# morkscam.net
KiCad netlist of a schematic drawn in EAGLE
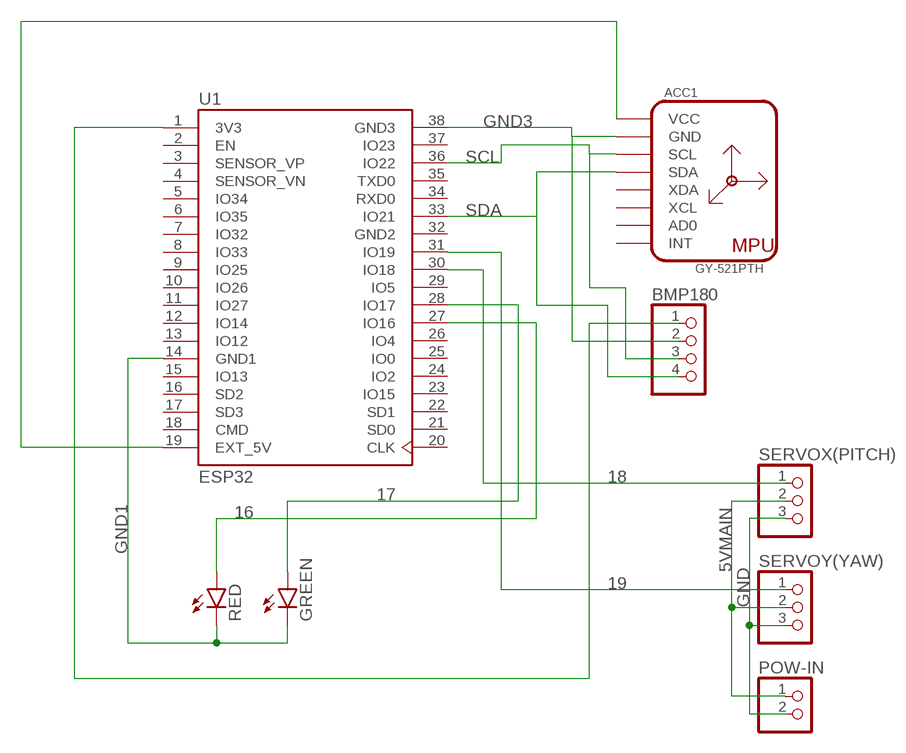
[diagram p0: schematic, sheet 1]

(export (version "E")
  (design (tool "Eeschema 10.0.6"))
  (components
    (comp (ref "ACC1")
      (value "GY-521PTH")
      (footprint "eagle-import:GY-521")
      (fields (field (name "MF") "GODREAM FORDREAM CO., LIMITED") (field (name "MP") "GY-521"))
      (libsource (lib "eagle-import") (part "GY-521PTH"))
    )
    (comp (ref "BMP180")
      (value "PINHD-1X4")
      (footprint "eagle-import:1X04")
      (libsource (lib "eagle-import") (part "PINHD-1X4"))
    )
    (comp (ref "GREEN")
      (value "LED3MM")
      (footprint "eagle-import:LED3MM")
      (libsource (lib "eagle-import") (part "LED3MM"))
    )
    (comp (ref "POW-IN")
      (value "PINHD-1X2")
      (footprint "eagle-import:1X02")
      (libsource (lib "eagle-import") (part "PINHD-1X2"))
    )
    (comp (ref "RED")
      (value "LED3MM")
      (footprint "eagle-import:LED3MM")
      (libsource (lib "eagle-import") (part "LED3MM"))
    )
    (comp (ref "SERVOX(PITCH)")
      (value "PINHD-1X3")
      (footprint "eagle-import:1X03")
      (libsource (lib "eagle-import") (part "PINHD-1X3"))
    )
    (comp (ref "SERVOY(YAW)")
      (value "PINHD-1X3")
      (footprint "eagle-import:1X03")
      (libsource (lib "eagle-import") (part "PINHD-1X3"))
    )
    (comp (ref "U1")
      (value "ESP32")
      (footprint "eagle-import:MODULE_ESP32-DEVKITC")
      (fields (field (name "MF") "Espressif Systems") (field (name "MP") "ESP32-DEVKITC"))
      (libsource (lib "eagle-import") (part "ESP32"))
    )
  )
  (nets
    (net (code "1") (name "/5VMAIN") (class "Default")
      (node (ref "POW-IN") (pin "1") (pinfunction "1_1") (pintype "passive"))
      (node (ref "SERVOX(PITCH)") (pin "2") (pinfunction "2_2") (pintype "passive"))
      (node (ref "SERVOY(YAW)") (pin "2") (pinfunction "2_2") (pintype "passive"))
    )
    (net (code "2") (name "/16") (class "Default")
      (node (ref "RED") (pin "A") (pinfunction "A_A") (pintype "passive"))
      (node (ref "U1") (pin "27") (pinfunction "IO16_27") (pintype "bidirectional"))
    )
    (net (code "3") (name "/17") (class "Default")
      (node (ref "GREEN") (pin "A") (pinfunction "A_A") (pintype "passive"))
      (node (ref "U1") (pin "28") (pinfunction "IO17_28") (pintype "bidirectional"))
    )
    (net (code "4") (name "/18") (class "Default")
      (node (ref "SERVOX(PITCH)") (pin "1") (pinfunction "1_1") (pintype "passive"))
      (node (ref "U1") (pin "30") (pinfunction "IO18_30") (pintype "bidirectional"))
    )
    (net (code "5") (name "/19") (class "Default")
      (node (ref "SERVOY(YAW)") (pin "1") (pinfunction "1_1") (pintype "passive"))
      (node (ref "U1") (pin "31") (pinfunction "IO19_31") (pintype "bidirectional"))
    )
    (net (code "6") (name "/GND") (class "Default")
      (node (ref "POW-IN") (pin "2") (pinfunction "2_2") (pintype "passive"))
      (node (ref "SERVOX(PITCH)") (pin "3") (pinfunction "3_3") (pintype "passive"))
      (node (ref "SERVOY(YAW)") (pin "3") (pinfunction "3_3") (pintype "passive"))
    )
    (net (code "7") (name "/GND1") (class "Default")
      (node (ref "GREEN") (pin "K") (pinfunction "C_K") (pintype "passive"))
      (node (ref "RED") (pin "K") (pinfunction "C_K") (pintype "passive"))
      (node (ref "U1") (pin "14") (pinfunction "GND1_14") (pintype "power_in"))
    )
    (net (code "8") (name "/GND2") (class "Default")
      (node (ref "U1") (pin "32") (pinfunction "GND2_32") (pintype "power_in"))
    )
    (net (code "9") (name "/GND3") (class "Default")
      (node (ref "ACC1") (pin "GND") (pinfunction "GND_GND") (pintype "power_in"))
      (node (ref "BMP180") (pin "2") (pinfunction "2_2") (pintype "passive"))
      (node (ref "U1") (pin "38") (pinfunction "GND3_38") (pintype "power_in"))
    )
    (net (code "10") (name "/SCL") (class "Default")
      (node (ref "ACC1") (pin "SCL") (pinfunction "SCL_SCL") (pintype "bidirectional"))
      (node (ref "BMP180") (pin "3") (pinfunction "3_3") (pintype "passive"))
      (node (ref "U1") (pin "36") (pinfunction "IO22_36") (pintype "bidirectional"))
    )
    (net (code "11") (name "/SDA") (class "Default")
      (node (ref "ACC1") (pin "SDA") (pinfunction "SDA_SDA") (pintype "bidirectional"))
      (node (ref "BMP180") (pin "4") (pinfunction "4_4") (pintype "passive"))
      (node (ref "U1") (pin "33") (pinfunction "IO21_33") (pintype "bidirectional"))
    )
    (net (code "12") (name "Net-(U1-3V3)") (class "Default")
      (node (ref "BMP180") (pin "1") (pinfunction "1_1") (pintype "passive"))
      (node (ref "U1") (pin "1") (pinfunction "3V3_1") (pintype "power_in"))
    )
    (net (code "13") (name "Net-(U1-EXT_5V)") (class "Default")
      (node (ref "ACC1") (pin "VCC") (pinfunction "VCC_VCC") (pintype "power_in"))
      (node (ref "U1") (pin "19") (pinfunction "EXT_5V_19") (pintype "power_in"))
    )
    (net (code "14") (name "unconnected-(ACC1-PadAD0)") (class "Default")
      (node (ref "ACC1") (pin "AD0") (pinfunction "AD0_AD0") (pintype "bidirectional"))
    )
    (net (code "15") (name "unconnected-(ACC1-PadINT)") (class "Default")
      (node (ref "ACC1") (pin "INT") (pinfunction "INT_INT") (pintype "bidirectional"))
    )
    (net (code "16") (name "unconnected-(ACC1-PadXCL)") (class "Default")
      (node (ref "ACC1") (pin "XCL") (pinfunction "XCL_XCL") (pintype "bidirectional"))
    )
    (net (code "17") (name "unconnected-(ACC1-PadXDA)") (class "Default")
      (node (ref "ACC1") (pin "XDA") (pinfunction "XDA_XDA") (pintype "bidirectional"))
    )
    (net (code "18") (name "unconnected-(U1-CLK-Pad20)") (class "Default")
      (node (ref "U1") (pin "20") (pinfunction "CLK_20") (pintype "input"))
    )
    (net (code "19") (name "unconnected-(U1-CMD-Pad18)") (class "Default")
      (node (ref "U1") (pin "18") (pinfunction "CMD_18") (pintype "bidirectional"))
    )
    (net (code "20") (name "unconnected-(U1-EN-Pad2)") (class "Default")
      (node (ref "U1") (pin "2") (pinfunction "EN_2") (pintype "input"))
    )
    (net (code "21") (name "unconnected-(U1-IO0-Pad25)") (class "Default")
      (node (ref "U1") (pin "25") (pinfunction "IO0_25") (pintype "bidirectional"))
    )
    (net (code "22") (name "unconnected-(U1-IO2-Pad24)") (class "Default")
      (node (ref "U1") (pin "24") (pinfunction "IO2_24") (pintype "bidirectional"))
    )
    (net (code "23") (name "unconnected-(U1-IO4-Pad26)") (class "Default")
      (node (ref "U1") (pin "26") (pinfunction "IO4_26") (pintype "bidirectional"))
    )
    (net (code "24") (name "unconnected-(U1-IO5-Pad29)") (class "Default")
      (node (ref "U1") (pin "29") (pinfunction "IO5_29") (pintype "bidirectional"))
    )
    (net (code "25") (name "unconnected-(U1-IO12-Pad13)") (class "Default")
      (node (ref "U1") (pin "13") (pinfunction "IO12_13") (pintype "bidirectional"))
    )
    (net (code "26") (name "unconnected-(U1-IO13-Pad15)") (class "Default")
      (node (ref "U1") (pin "15") (pinfunction "IO13_15") (pintype "bidirectional"))
    )
    (net (code "27") (name "unconnected-(U1-IO14-Pad12)") (class "Default")
      (node (ref "U1") (pin "12") (pinfunction "IO14_12") (pintype "bidirectional"))
    )
    (net (code "28") (name "unconnected-(U1-IO15-Pad23)") (class "Default")
      (node (ref "U1") (pin "23") (pinfunction "IO15_23") (pintype "bidirectional"))
    )
    (net (code "29") (name "unconnected-(U1-IO23-Pad37)") (class "Default")
      (node (ref "U1") (pin "37") (pinfunction "IO23_37") (pintype "bidirectional"))
    )
    (net (code "30") (name "unconnected-(U1-IO25-Pad9)") (class "Default")
      (node (ref "U1") (pin "9") (pinfunction "IO25_9") (pintype "bidirectional"))
    )
    (net (code "31") (name "unconnected-(U1-IO26-Pad10)") (class "Default")
      (node (ref "U1") (pin "10") (pinfunction "IO26_10") (pintype "bidirectional"))
    )
    (net (code "32") (name "unconnected-(U1-IO27-Pad11)") (class "Default")
      (node (ref "U1") (pin "11") (pinfunction "IO27_11") (pintype "bidirectional"))
    )
    (net (code "33") (name "unconnected-(U1-IO32-Pad7)") (class "Default")
      (node (ref "U1") (pin "7") (pinfunction "IO32_7") (pintype "bidirectional"))
    )
    (net (code "34") (name "unconnected-(U1-IO33-Pad8)") (class "Default")
      (node (ref "U1") (pin "8") (pinfunction "IO33_8") (pintype "bidirectional"))
    )
    (net (code "35") (name "unconnected-(U1-IO34-Pad5)") (class "Default")
      (node (ref "U1") (pin "5") (pinfunction "IO34_5") (pintype "bidirectional"))
    )
    (net (code "36") (name "unconnected-(U1-IO35-Pad6)") (class "Default")
      (node (ref "U1") (pin "6") (pinfunction "IO35_6") (pintype "bidirectional"))
    )
    (net (code "37") (name "unconnected-(U1-RXD0-Pad34)") (class "Default")
      (node (ref "U1") (pin "34") (pinfunction "RXD0_34") (pintype "input"))
    )
    (net (code "38") (name "unconnected-(U1-SD0-Pad21)") (class "Default")
      (node (ref "U1") (pin "21") (pinfunction "SD0_21") (pintype "bidirectional"))
    )
    (net (code "39") (name "unconnected-(U1-SD1-Pad22)") (class "Default")
      (node (ref "U1") (pin "22") (pinfunction "SD1_22") (pintype "bidirectional"))
    )
    (net (code "40") (name "unconnected-(U1-SD2-Pad16)") (class "Default")
      (node (ref "U1") (pin "16") (pinfunction "SD2_16") (pintype "bidirectional"))
    )
    (net (code "41") (name "unconnected-(U1-SD3-Pad17)") (class "Default")
      (node (ref "U1") (pin "17") (pinfunction "SD3_17") (pintype "bidirectional"))
    )
    (net (code "42") (name "unconnected-(U1-SENSOR_VN-Pad4)") (class "Default")
      (node (ref "U1") (pin "4") (pinfunction "SENSOR_VN_4") (pintype "input"))
    )
    (net (code "43") (name "unconnected-(U1-SENSOR_VP-Pad3)") (class "Default")
      (node (ref "U1") (pin "3") (pinfunction "SENSOR_VP_3") (pintype "input"))
    )
    (net (code "44") (name "unconnected-(U1-TXD0-Pad35)") (class "Default")
      (node (ref "U1") (pin "35") (pinfunction "TXD0_35") (pintype "output"))
    )
  )
)
